# Schematic_v1.net
KiCad netlist of a schematic drawn in EAGLE
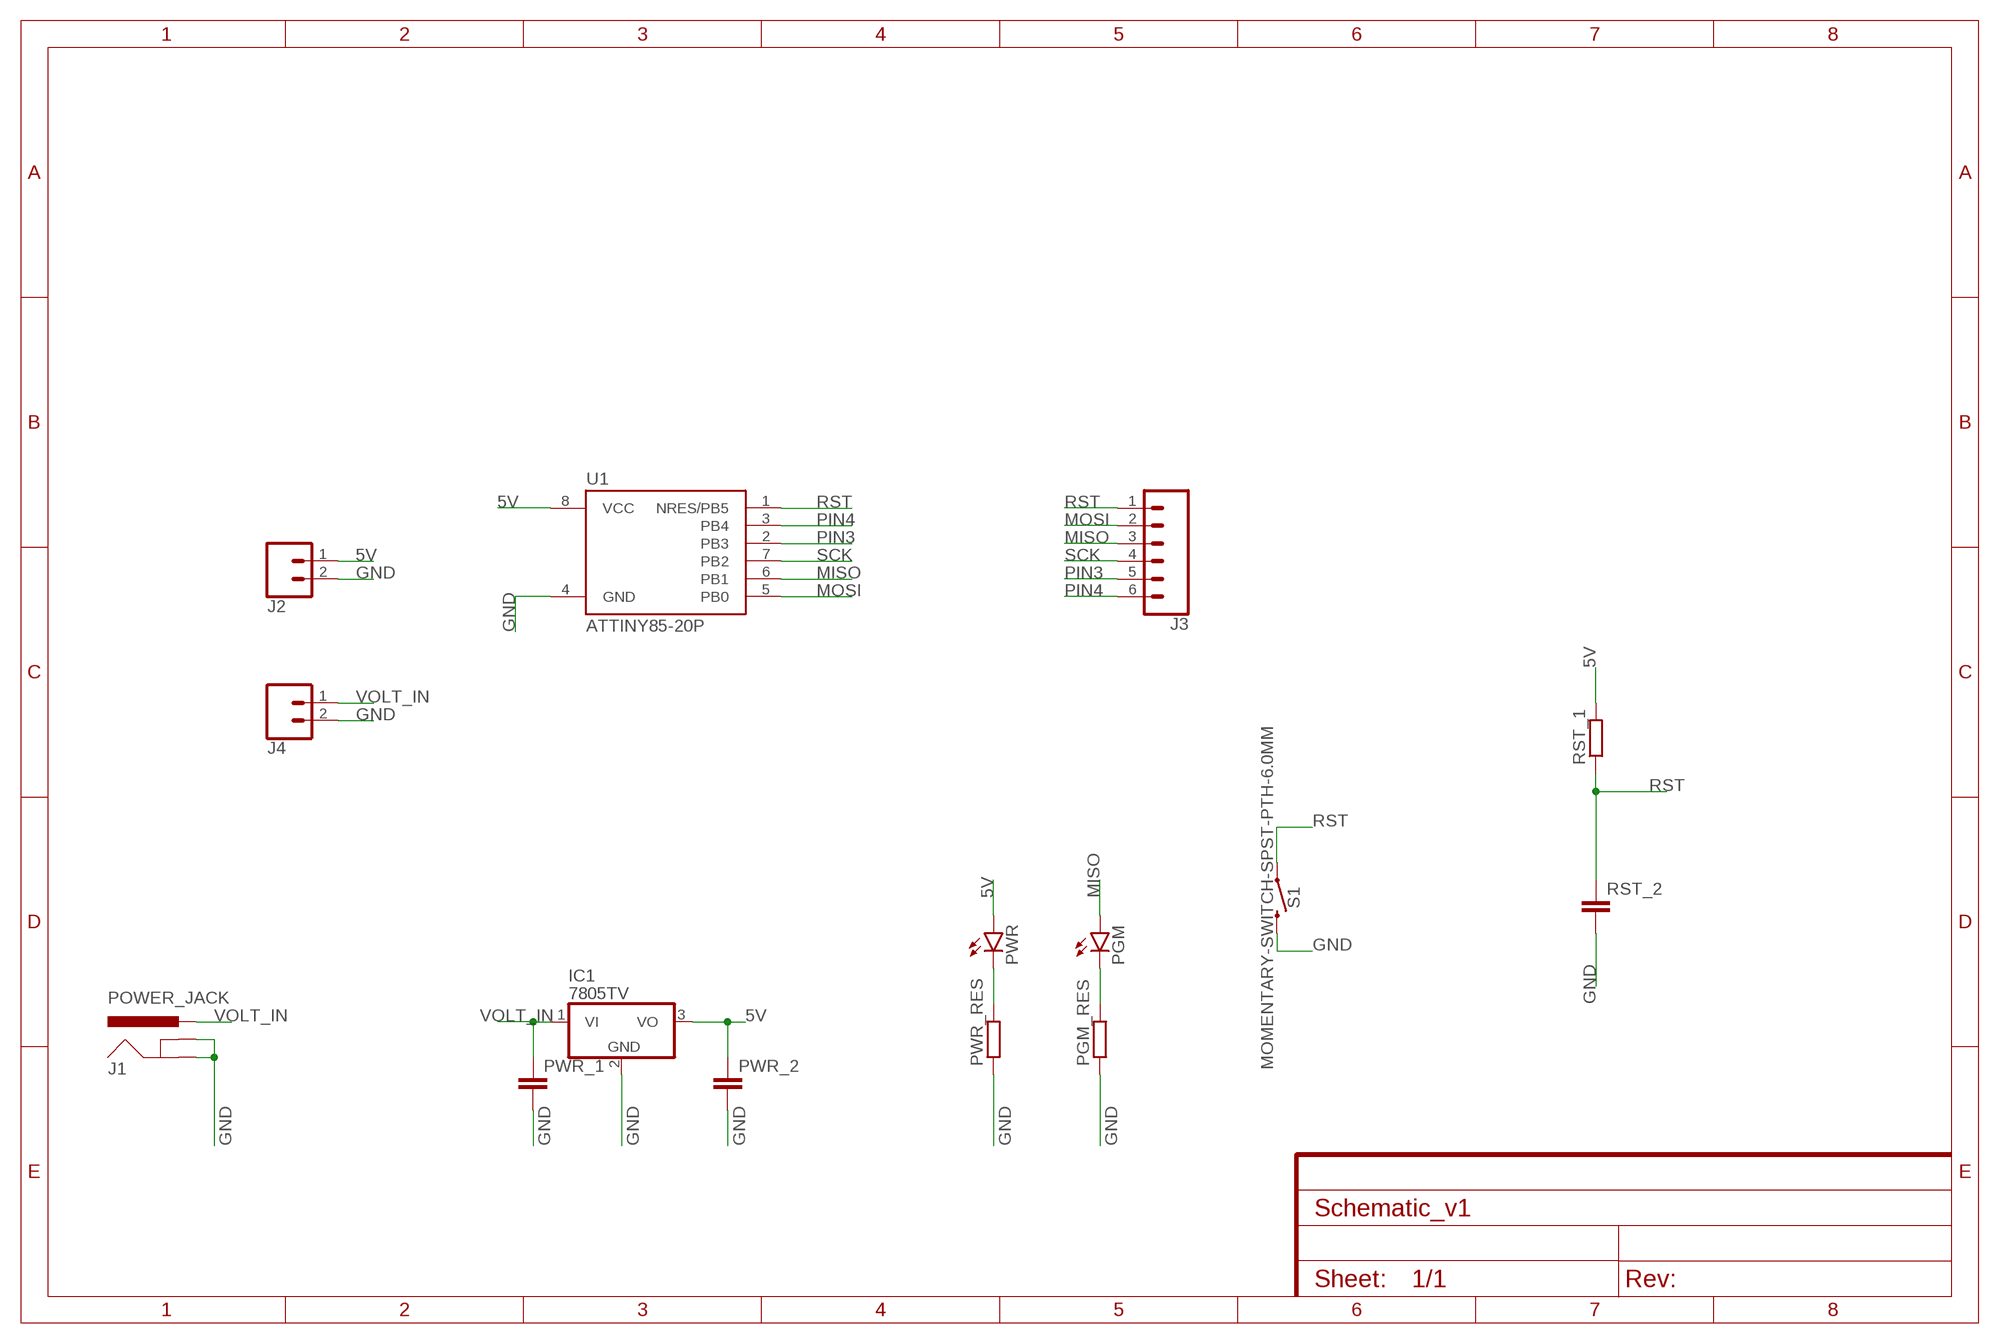
[diagram p0: schematic, sheet 1]

(export (version "E")
  (design (tool "Eeschema 10.0.6"))
  (components
    (comp (ref "IC1")
      (value "7805TV")
      (footprint "eagle-import:TO220V")
      (libsource (lib "eagle-import") (part "78TV05"))
    )
    (comp (ref "J1")
      (value "POWER_JACK")
      (footprint "eagle-import:POWER_JACK_PTH")
      (libsource (lib "eagle-import") (part "POWER_JACK"))
    )
    (comp (ref "J2")
      (value "CONN_021X02_NO_SILK")
      (footprint "eagle-import:1X02_NO_SILK")
      (libsource (lib "eagle-import") (part "CONN_021X02_NO_SILK"))
    )
    (comp (ref "J3")
      (value "CONN_06NO_SILK_NO_POP")
      (footprint "eagle-import:1X06_NO_SILK")
      (libsource (lib "eagle-import") (part "CONN_06NO_SILK_NO_POP"))
    )
    (comp (ref "J4")
      (value "CONN_021X02_NO_SILK")
      (footprint "eagle-import:1X02_NO_SILK")
      (libsource (lib "eagle-import") (part "CONN_021X02_NO_SILK"))
    )
    (comp (ref "PGM")
      (value "LED3MM")
      (footprint "eagle-import:LED3MM")
      (libsource (lib "eagle-import") (part "LED3MM"))
    )
    (comp (ref "PGM_RES")
      (value "R-EU_0207/2V")
      (footprint "eagle-import:0207_2V")
      (libsource (lib "eagle-import") (part "R-EU_0207/2V"))
    )
    (comp (ref "PWR")
      (value "LED3MM")
      (footprint "eagle-import:LED3MM")
      (libsource (lib "eagle-import") (part "LED3MM"))
    )
    (comp (ref "PWR_1")
      (value "C-EU025-025X050")
      (footprint "eagle-import:C025-025X050")
      (libsource (lib "eagle-import") (part "C-EU025-025X050"))
    )
    (comp (ref "PWR_2")
      (value "C-EU025-025X050")
      (footprint "eagle-import:C025-025X050")
      (libsource (lib "eagle-import") (part "C-EU025-025X050"))
    )
    (comp (ref "PWR_RES")
      (value "R-EU_0207/2V")
      (footprint "eagle-import:0207_2V")
      (libsource (lib "eagle-import") (part "R-EU_0207/2V"))
    )
    (comp (ref "RST_1")
      (value "R-EU_0207/2V")
      (footprint "eagle-import:0207_2V")
      (libsource (lib "eagle-import") (part "R-EU_0207/2V"))
    )
    (comp (ref "RST_2")
      (value "C-EU025-025X050")
      (footprint "eagle-import:C025-025X050")
      (libsource (lib "eagle-import") (part "C-EU025-025X050"))
    )
    (comp (ref "S1")
      (value "MOMENTARY-SWITCH-SPST-PTH-6.0MM")
      (footprint "eagle-import:TACTILE_SWITCH_PTH_6.0MM")
      (libsource (lib "eagle-import") (part "MOMENTARY-SWITCH-SPST-PTH-6.0MM"))
    )
    (comp (ref "U1")
      (value "ATTINY85-20P")
      (footprint "eagle-import:PDIP08_300MIL")
      (libsource (lib "eagle-import") (part "ATTINY85P-20"))
    )
  )
  (nets
    (net (code "1") (name "/5V") (class "Default")
      (node (ref "IC1") (pin "3") (pinfunction "VO_3") (pintype "passive"))
      (node (ref "J2") (pin "1") (pinfunction "1_1") (pintype "passive"))
      (node (ref "PWR") (pin "A") (pinfunction "A_A") (pintype "passive"))
      (node (ref "PWR_2") (pin "1") (pinfunction "1_1") (pintype "passive"))
      (node (ref "RST_1") (pin "2") (pinfunction "2_2") (pintype "passive"))
      (node (ref "U1") (pin "8") (pinfunction "VCC_8") (pintype "power_in"))
    )
    (net (code "2") (name "/GND") (class "Default")
      (node (ref "IC1") (pin "2") (pinfunction "GND_2") (pintype "passive"))
      (node (ref "J1") (pin "GND") (pinfunction "GND_GND") (pintype "bidirectional"))
      (node (ref "J1") (pin "GNDBREAK") (pinfunction "GNDBREAK_GNDBREAK") (pintype "bidirectional"))
      (node (ref "J2") (pin "2") (pinfunction "2_2") (pintype "passive"))
      (node (ref "J4") (pin "2") (pinfunction "2_2") (pintype "passive"))
      (node (ref "PGM_RES") (pin "1") (pinfunction "1_1") (pintype "passive"))
      (node (ref "PWR_1") (pin "2") (pinfunction "2_2") (pintype "passive"))
      (node (ref "PWR_2") (pin "2") (pinfunction "2_2") (pintype "passive"))
      (node (ref "PWR_RES") (pin "1") (pinfunction "1_1") (pintype "passive"))
      (node (ref "RST_2") (pin "2") (pinfunction "2_2") (pintype "passive"))
      (node (ref "S1") (pin "3") (pinfunction "2_3") (pintype "passive"))
      (node (ref "U1") (pin "4") (pinfunction "GND_4") (pintype "power_in"))
    )
    (net (code "3") (name "/MISO") (class "Default")
      (node (ref "J3") (pin "3") (pinfunction "3_3") (pintype "passive"))
      (node (ref "PGM") (pin "A") (pinfunction "A_A") (pintype "passive"))
      (node (ref "U1") (pin "6") (pinfunction "PB1_6") (pintype "bidirectional"))
    )
    (net (code "4") (name "/MOSI") (class "Default")
      (node (ref "J3") (pin "2") (pinfunction "2_2") (pintype "passive"))
      (node (ref "U1") (pin "5") (pinfunction "PB0_5") (pintype "bidirectional"))
    )
    (net (code "5") (name "/PIN3") (class "Default")
      (node (ref "J3") (pin "5") (pinfunction "5_5") (pintype "passive"))
      (node (ref "U1") (pin "2") (pinfunction "PB3_2") (pintype "bidirectional"))
    )
    (net (code "6") (name "/PIN4") (class "Default")
      (node (ref "J3") (pin "6") (pinfunction "6_6") (pintype "passive"))
      (node (ref "U1") (pin "3") (pinfunction "PB4_3") (pintype "bidirectional"))
    )
    (net (code "7") (name "/RST") (class "Default")
      (node (ref "J3") (pin "1") (pinfunction "1_1") (pintype "passive"))
      (node (ref "RST_1") (pin "1") (pinfunction "1_1") (pintype "passive"))
      (node (ref "RST_2") (pin "1") (pinfunction "1_1") (pintype "passive"))
      (node (ref "S1") (pin "1") (pinfunction "1_1") (pintype "passive"))
      (node (ref "U1") (pin "1") (pinfunction "NRES/PB5_1") (pintype "bidirectional"))
    )
    (net (code "8") (name "/SCK") (class "Default")
      (node (ref "J3") (pin "4") (pinfunction "4_4") (pintype "passive"))
      (node (ref "U1") (pin "7") (pinfunction "PB2_7") (pintype "bidirectional"))
    )
    (net (code "9") (name "/VOLT_IN") (class "Default")
      (node (ref "IC1") (pin "1") (pinfunction "VI_1") (pintype "input"))
      (node (ref "J1") (pin "PWR") (pinfunction "PWR_PWR") (pintype "bidirectional"))
      (node (ref "J4") (pin "1") (pinfunction "1_1") (pintype "passive"))
      (node (ref "PWR_1") (pin "1") (pinfunction "1_1") (pintype "passive"))
    )
    (net (code "10") (name "Net-(PGM-C)") (class "Default")
      (node (ref "PGM") (pin "K") (pinfunction "C_K") (pintype "passive"))
      (node (ref "PGM_RES") (pin "2") (pinfunction "2_2") (pintype "passive"))
    )
    (net (code "11") (name "Net-(PWR-C)") (class "Default")
      (node (ref "PWR") (pin "K") (pinfunction "C_K") (pintype "passive"))
      (node (ref "PWR_RES") (pin "2") (pinfunction "2_2") (pintype "passive"))
    )
  )
)
